# Volant5_PIC32MX_circuit_1_0.net
KiCad netlist of a schematic drawn in Altium Designer
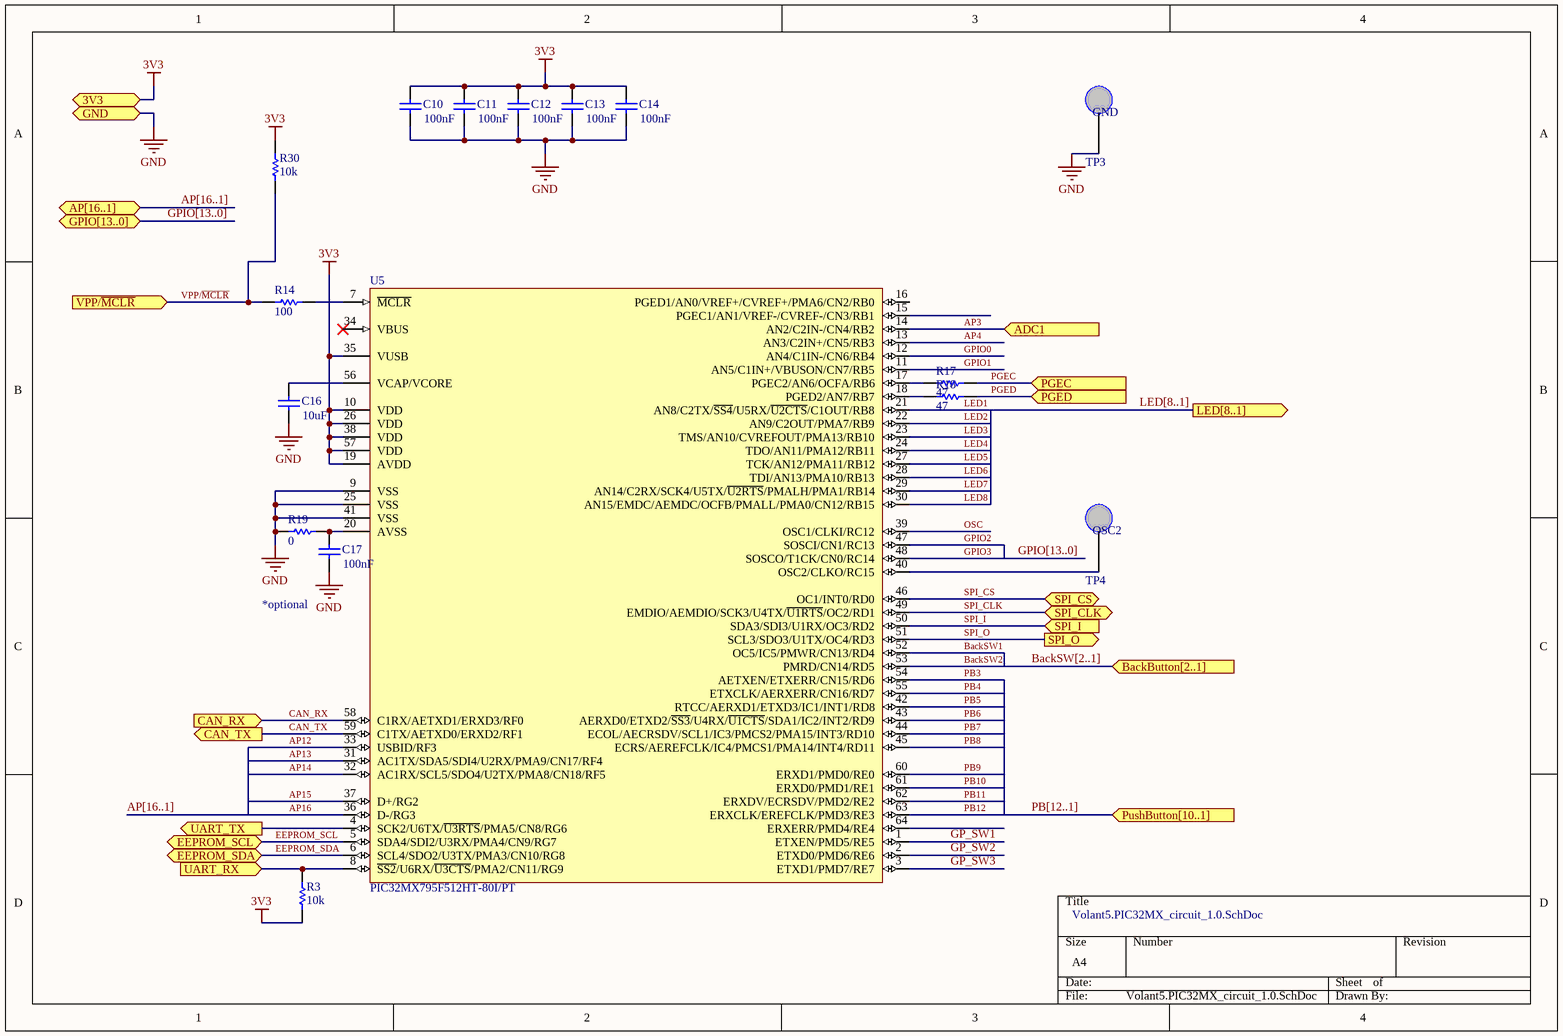
[diagram p0: Volant5.PIC32MX_circuit_1.0.SchDoc]

(export (version "E")
  (design (tool "Eeschema 10.0.6"))
  (components
    (comp (ref "C10")
      (value "100nF")
      (footprint "CS-0603")
      (fields (field (name "TOLERANCE") "10%") (field (name "Comment") "CS - CAPACITOR"))
      (libsource (lib "CHINOOK_LIBRARY") (part "CS - CAPACITOR"))
    )
    (comp (ref "C11")
      (value "100nF")
      (footprint "CS-0603")
      (fields (field (name "TOLERANCE") "10%") (field (name "Comment") "CS - CAPACITOR"))
      (libsource (lib "CHINOOK_LIBRARY") (part "CS - CAPACITOR"))
    )
    (comp (ref "C12")
      (value "100nF")
      (footprint "CS-0603")
      (fields (field (name "TOLERANCE") "10%") (field (name "Comment") "CS - CAPACITOR"))
      (libsource (lib "CHINOOK_LIBRARY") (part "CS - CAPACITOR"))
    )
    (comp (ref "C13")
      (value "100nF")
      (footprint "CS-0603")
      (fields (field (name "TOLERANCE") "10%") (field (name "Comment") "CS - CAPACITOR"))
      (libsource (lib "CHINOOK_LIBRARY") (part "CS - CAPACITOR"))
    )
    (comp (ref "C14")
      (value "100nF")
      (footprint "CS-0603")
      (fields (field (name "TOLERANCE") "10%") (field (name "Comment") "CS - CAPACITOR"))
      (libsource (lib "CHINOOK_LIBRARY") (part "CS - CAPACITOR"))
    )
    (comp (ref "C16")
      (value "10uF")
      (footprint "CS-0603")
      (fields (field (name "TOLERANCE") "10%") (field (name "Comment") "CS - CAPACITOR"))
      (libsource (lib "CHINOOK_LIBRARY") (part "CS - CAPACITOR"))
    )
    (comp (ref "C17")
      (value "100nF")
      (footprint "CS-0603")
      (fields (field (name "TOLERANCE") "10%") (field (name "Comment") "CS - CAPACITOR"))
      (libsource (lib "CHINOOK_LIBRARY") (part "CS - CAPACITOR"))
    )
    (comp (ref "R3")
      (value "10k")
      (footprint "RS-0402")
      (fields
        (field (name "TOLERANCE") "RES TOL")
        (field (name "POWER") "RES POWER")
        (field (name "Comment") "RS - RESISTOR")
      )
      (libsource (lib "CHINOOK_LIBRARY") (part "RS - RESISTOR"))
    )
    (comp (ref "R14")
      (value "100")
      (footprint "RS-0603")
      (fields
        (field (name "TOLERANCE") "RES TOL")
        (field (name "POWER") "RES POWER")
        (field (name "Comment") "RS - RESISTOR")
      )
      (libsource (lib "CHINOOK_LIBRARY") (part "RS - RESISTOR"))
    )
    (comp (ref "R17")
      (value "47")
      (footprint "RS-0603")
      (fields
        (field (name "TOLERANCE") "RES TOL")
        (field (name "POWER") "RES POWER")
        (field (name "Comment") "RS - RESISTOR")
      )
      (libsource (lib "CHINOOK_LIBRARY") (part "RS - RESISTOR"))
    )
    (comp (ref "R18")
      (value "47")
      (footprint "RS-0603")
      (fields
        (field (name "TOLERANCE") "RES TOL")
        (field (name "POWER") "RES POWER")
        (field (name "Comment") "RS - RESISTOR")
      )
      (libsource (lib "CHINOOK_LIBRARY") (part "RS - RESISTOR"))
    )
    (comp (ref "R19")
      (value "0")
      (footprint "RS-0603")
      (fields
        (field (name "TOLERANCE") "RES TOL")
        (field (name "POWER") "RES POWER")
        (field (name "Comment") "RS - RESISTOR")
      )
      (libsource (lib "CHINOOK_LIBRARY") (part "RS - RESISTOR"))
    )
    (comp (ref "R30")
      (value "10k")
      (footprint "RS-0603")
      (fields
        (field (name "TOLERANCE") "RES TOL")
        (field (name "POWER") "RES POWER")
        (field (name "Comment") "RS - RESISTOR")
      )
      (libsource (lib "CHINOOK_LIBRARY") (part "RS - RESISTOR"))
    )
    (comp (ref "TP3")
      (value "GND")
      (footprint "TP - VERTICAL")
      (libsource (lib "CHINOOK_LIBRARY") (part "TP - Test point vertical"))
    )
    (comp (ref "TP4")
      (value "OSC2")
      (footprint "TP - VERTICAL")
      (libsource (lib "CHINOOK_LIBRARY") (part "TP - Test point vertical"))
    )
    (comp (ref "U5")
      (value "PIC32MX795F512HT-80I/PT")
      (footprint "IC-TQFP-64")
      (fields (field (name "MANUFACTURER") "Microchip"))
      (libsource (lib "CHINOOK_LIBRARY") (part "IC - PIC32MX795F512HT-80I/PT"))
    )
  )
  (nets
    (net (code "22") (name "/AP3") (class "Default")
      (node (ref "U5") (pin "14") (pinfunction "AN2/C2IN-/CN4/RB2_14") (pintype "bidirectional"))
    )
    (net (code "23") (name "/AP4") (class "Default")
      (node (ref "U5") (pin "13") (pinfunction "AN3/C2IN+/CN5/RB3_13") (pintype "bidirectional"))
    )
    (net (code "24") (name "/AP12") (class "Default")
      (node (ref "U5") (pin "33") (pinfunction "USBID/RF3_33") (pintype "bidirectional"))
    )
    (net (code "25") (name "/AP13") (class "Default")
      (node (ref "U5") (pin "31") (pinfunction "AC1TX/SDA5/SDI4/U2RX/PMA9/CN17/RF4_31") (pintype "bidirectional"))
    )
    (net (code "26") (name "/AP14") (class "Default")
      (node (ref "U5") (pin "32") (pinfunction "AC1RX/SCL5/SDO4/U2TX/PMA8/CN18/RF5_32") (pintype "bidirectional"))
    )
    (net (code "27") (name "/AP15") (class "Default")
      (node (ref "U5") (pin "37") (pinfunction "D+/RG2_37") (pintype "bidirectional"))
    )
    (net (code "28") (name "/AP16") (class "Default")
      (node (ref "U5") (pin "36") (pinfunction "D-/RG3_36") (pintype "bidirectional"))
    )
    (net (code "30") (name "/BackSW1") (class "Default")
      (node (ref "U5") (pin "52") (pinfunction "OC5/IC5/PMWR/CN13/RD4_52") (pintype "bidirectional"))
    )
    (net (code "31") (name "/BackSW2") (class "Default")
      (node (ref "U5") (pin "53") (pinfunction "PMRD/CN14/RD5_53") (pintype "bidirectional"))
    )
    (net (code "33") (name "/CAN_RX") (class "Default")
      (node (ref "U5") (pin "58") (pinfunction "C1RX/AETXD1/ERXD3/RF0_58") (pintype "bidirectional"))
    )
    (net (code "34") (name "/CAN_TX") (class "Default")
      (node (ref "U5") (pin "59") (pinfunction "C1TX/AETXD0/ERXD2/RF1_59") (pintype "bidirectional"))
    )
    (net (code "35") (name "/EEPROM_SCL") (class "Default")
      (node (ref "U5") (pin "5") (pinfunction "SDA4/SDI2/U3RX/PMA4/CN9/RG7_5") (pintype "bidirectional"))
    )
    (net (code "36") (name "/EEPROM_SDA") (class "Default")
      (node (ref "U5") (pin "6") (pinfunction "SCL4/SDO2/U3TX/PMA3/CN10/RG8_6") (pintype "bidirectional"))
    )
    (net (code "37") (name "/GPIO0") (class "Default")
      (node (ref "U5") (pin "12") (pinfunction "AN4/C1IN-/CN6/RB4_12") (pintype "bidirectional"))
    )
    (net (code "38") (name "/GPIO1") (class "Default")
      (node (ref "U5") (pin "11") (pinfunction "AN5/C1IN+/VBUSON/CN7/RB5_11") (pintype "bidirectional"))
    )
    (net (code "39") (name "/GPIO2") (class "Default")
      (node (ref "U5") (pin "47") (pinfunction "SOSCI/CN1/RC13_47") (pintype "bidirectional"))
    )
    (net (code "40") (name "/GPIO3") (class "Default")
      (node (ref "U5") (pin "48") (pinfunction "SOSCO/T1CK/CN0/RC14_48") (pintype "bidirectional"))
    )
    (net (code "42") (name "/GP_SW1") (class "Default")
      (node (ref "U5") (pin "1") (pinfunction "ETXEN/PMD5/RE5_1") (pintype "bidirectional"))
    )
    (net (code "43") (name "/GP_SW2") (class "Default")
      (node (ref "U5") (pin "2") (pinfunction "ETXD0/PMD6/RE6_2") (pintype "bidirectional"))
    )
    (net (code "44") (name "/GP_SW3") (class "Default")
      (node (ref "U5") (pin "3") (pinfunction "ETXD1/PMD7/RE7_3") (pintype "bidirectional"))
    )
    (net (code "45") (name "/LED1") (class "Default")
      (node (ref "U5") (pin "21") (pinfunction "AN8/C2TX/~{SS4}/U5RX/~{U2CTS}/C1OUT/RB8_21") (pintype "bidirectional"))
    )
    (net (code "46") (name "/LED2") (class "Default")
      (node (ref "U5") (pin "22") (pinfunction "AN9/C2OUT/PMA7/RB9_22") (pintype "bidirectional"))
    )
    (net (code "47") (name "/LED3") (class "Default")
      (node (ref "U5") (pin "23") (pinfunction "TMS/AN10/CVREFOUT/PMA13/RB10_23") (pintype "bidirectional"))
    )
    (net (code "48") (name "/LED4") (class "Default")
      (node (ref "U5") (pin "24") (pinfunction "TDO/AN11/PMA12/RB11_24") (pintype "bidirectional"))
    )
    (net (code "49") (name "/LED5") (class "Default")
      (node (ref "U5") (pin "27") (pinfunction "TCK/AN12/PMA11/RB12_27") (pintype "bidirectional"))
    )
    (net (code "50") (name "/LED6") (class "Default")
      (node (ref "U5") (pin "28") (pinfunction "TDI/AN13/PMA10/RB13_28") (pintype "bidirectional"))
    )
    (net (code "51") (name "/LED7") (class "Default")
      (node (ref "U5") (pin "29") (pinfunction "AN14/C2RX/SCK4/U5TX/~{U2RTS}/PMALH/PMA1/RB14_29") (pintype "bidirectional"))
    )
    (net (code "52") (name "/LED8") (class "Default")
      (node (ref "U5") (pin "30") (pinfunction "AN15/EMDC/AEMDC/OCFB/PMALL/PMA0/CN12/RB15_30") (pintype "bidirectional"))
    )
    (net (code "54") (name "/OSC") (class "Default")
      (node (ref "U5") (pin "39") (pinfunction "OSC1/CLKI/RC12_39") (pintype "bidirectional"))
    )
    (net (code "55") (name "/PB3") (class "Default")
      (node (ref "U5") (pin "54") (pinfunction "AETXEN/ETXERR/CN15/RD6_54") (pintype "bidirectional"))
    )
    (net (code "56") (name "/PB4") (class "Default")
      (node (ref "U5") (pin "55") (pinfunction "ETXCLK/AERXERR/CN16/RD7_55") (pintype "bidirectional"))
    )
    (net (code "57") (name "/PB5") (class "Default")
      (node (ref "U5") (pin "42") (pinfunction "RTCC/AERXD1/ETXD3/IC1/INT1/RD8_42") (pintype "bidirectional"))
    )
    (net (code "58") (name "/PB6") (class "Default")
      (node (ref "U5") (pin "43") (pinfunction "AERXD0/ETXD2/~{SS3}/U4RX/~{U1CTS}/SDA1/IC2/INT2/RD9_43") (pintype "bidirectional"))
    )
    (net (code "59") (name "/PB7") (class "Default")
      (node (ref "U5") (pin "44") (pinfunction "ECOL/AECRSDV/SCL1/IC3/PMCS2/PMA15/INT3/RD10_44") (pintype "bidirectional"))
    )
    (net (code "60") (name "/PB8") (class "Default")
      (node (ref "U5") (pin "45") (pinfunction "ECRS/AEREFCLK/IC4/PMCS1/PMA14/INT4/RD11_45") (pintype "bidirectional"))
    )
    (net (code "61") (name "/PB9") (class "Default")
      (node (ref "U5") (pin "60") (pinfunction "ERXD1/PMD0/RE0_60") (pintype "bidirectional"))
    )
    (net (code "62") (name "/PB10") (class "Default")
      (node (ref "U5") (pin "61") (pinfunction "ERXD0/PMD1/RE1_61") (pintype "bidirectional"))
    )
    (net (code "63") (name "/PB11") (class "Default")
      (node (ref "U5") (pin "62") (pinfunction "ERXDV/ECRSDV/PMD2/RE2_62") (pintype "bidirectional"))
    )
    (net (code "64") (name "/PB12") (class "Default")
      (node (ref "U5") (pin "63") (pinfunction "ERXCLK/EREFCLK/PMD3/RE3_63") (pintype "bidirectional"))
    )
    (net (code "66") (name "/PGEC") (class "Default")
      (node (ref "R17") (pin "1") (pinfunction "1_1") (pintype "passive"))
    )
    (net (code "67") (name "/PGED") (class "Default")
      (node (ref "R18") (pin "1") (pinfunction "1_1") (pintype "passive"))
    )
    (net (code "68") (name "/SPI_CLK") (class "Default")
      (node (ref "U5") (pin "49") (pinfunction "EMDIO/AEMDIO/SCK3/U4TX/~{U1RTS}/OC2/RD1_49") (pintype "bidirectional"))
    )
    (net (code "69") (name "/SPI_CS") (class "Default")
      (node (ref "U5") (pin "46") (pinfunction "OC1/INT0/RD0_46") (pintype "bidirectional"))
    )
    (net (code "70") (name "/SPI_I") (class "Default")
      (node (ref "U5") (pin "50") (pinfunction "SDA3/SDI3/U1RX/OC3/RD2_50") (pintype "bidirectional"))
    )
    (net (code "71") (name "/SPI_O") (class "Default")
      (node (ref "U5") (pin "51") (pinfunction "SCL3/SDO3/U1TX/OC4/RD3_51") (pintype "bidirectional"))
    )
    (net (code "72") (name "/UART_RX") (class "Default")
      (node (ref "R3") (pin "2") (pinfunction "2_2") (pintype "passive"))
      (node (ref "U5") (pin "8") (pinfunction "~{SS2}/U6RX/~{U3CTS}/PMA2/CN11/RG9_8") (pintype "bidirectional"))
    )
    (net (code "73") (name "/UART_TX") (class "Default")
      (node (ref "U5") (pin "4") (pinfunction "SCK2/U6TX/~{U3RTS}/PMA5/CN8/RG6_4") (pintype "bidirectional"))
    )
    (net (code "74") (name "/VPP{slash}~{MCLR}") (class "Default")
      (node (ref "R14") (pin "2") (pinfunction "2_2") (pintype "passive"))
      (node (ref "R30") (pin "1") (pinfunction "1_1") (pintype "passive"))
    )
    (net (code "75") (name "3V3") (class "Default")
      (node (ref "C10") (pin "2") (pinfunction "2_2") (pintype "passive"))
      (node (ref "C11") (pin "2") (pinfunction "2_2") (pintype "passive"))
      (node (ref "C12") (pin "2") (pinfunction "2_2") (pintype "passive"))
      (node (ref "C13") (pin "2") (pinfunction "2_2") (pintype "passive"))
      (node (ref "C14") (pin "2") (pinfunction "2_2") (pintype "passive"))
      (node (ref "R3") (pin "1") (pinfunction "1_1") (pintype "passive"))
      (node (ref "R30") (pin "2") (pinfunction "2_2") (pintype "passive"))
      (node (ref "U5") (pin "10") (pinfunction "VDD_10") (pintype "power_in"))
      (node (ref "U5") (pin "19") (pinfunction "AVDD_19") (pintype "power_in"))
      (node (ref "U5") (pin "26") (pinfunction "VDD_26") (pintype "power_in"))
      (node (ref "U5") (pin "35") (pinfunction "VUSB_35") (pintype "power_in"))
      (node (ref "U5") (pin "38") (pinfunction "VDD_38") (pintype "power_in"))
      (node (ref "U5") (pin "57") (pinfunction "VDD_57") (pintype "power_in"))
    )
    (net (code "76") (name "GND") (class "Default")
      (node (ref "C10") (pin "1") (pinfunction "1_1") (pintype "passive"))
      (node (ref "C11") (pin "1") (pinfunction "1_1") (pintype "passive"))
      (node (ref "C12") (pin "1") (pinfunction "1_1") (pintype "passive"))
      (node (ref "C13") (pin "1") (pinfunction "1_1") (pintype "passive"))
      (node (ref "C14") (pin "1") (pinfunction "1_1") (pintype "passive"))
      (node (ref "C16") (pin "1") (pinfunction "1_1") (pintype "passive"))
      (node (ref "C17") (pin "1") (pinfunction "1_1") (pintype "passive"))
      (node (ref "R19") (pin "2") (pinfunction "2_2") (pintype "passive"))
      (node (ref "TP3") (pin "1") (pinfunction "1_1") (pintype "passive"))
      (node (ref "U5") (pin "25") (pinfunction "VSS_25") (pintype "power_in"))
      (node (ref "U5") (pin "41") (pinfunction "VSS_41") (pintype "power_in"))
      (node (ref "U5") (pin "9") (pinfunction "VSS_9") (pintype "power_in"))
    )
    (net (code "77") (name "Net-(U5-AVSS)") (class "Default")
      (node (ref "C17") (pin "2") (pinfunction "2_2") (pintype "passive"))
      (node (ref "R19") (pin "1") (pinfunction "1_1") (pintype "passive"))
      (node (ref "U5") (pin "20") (pinfunction "AVSS_20") (pintype "power_in"))
    )
    (net (code "78") (name "Net-(U5-OSC2{slash}CLKO{slash}RC15)") (class "Default")
      (node (ref "TP4") (pin "1") (pinfunction "1_1") (pintype "passive"))
      (node (ref "U5") (pin "40") (pinfunction "OSC2/CLKO/RC15_40") (pintype "bidirectional"))
    )
    (net (code "79") (name "Net-(U5-PGEC2{slash}AN6{slash}OCFA{slash}RB6)") (class "Default")
      (node (ref "R17") (pin "2") (pinfunction "2_2") (pintype "passive"))
      (node (ref "U5") (pin "17") (pinfunction "PGEC2/AN6/OCFA/RB6_17") (pintype "bidirectional"))
    )
    (net (code "80") (name "Net-(U5-PGED2{slash}AN7{slash}RB7)") (class "Default")
      (node (ref "R18") (pin "2") (pinfunction "2_2") (pintype "passive"))
      (node (ref "U5") (pin "18") (pinfunction "PGED2/AN7/RB7_18") (pintype "bidirectional"))
    )
    (net (code "81") (name "Net-(U5-VCAP{slash}VCORE)") (class "Default")
      (node (ref "C16") (pin "2") (pinfunction "2_2") (pintype "passive"))
      (node (ref "U5") (pin "56") (pinfunction "VCAP/VCORE_56") (pintype "power_in"))
    )
    (net (code "82") (name "Net-(U5-~{MCLR})") (class "Default")
      (node (ref "R14") (pin "1") (pinfunction "1_1") (pintype "passive"))
      (node (ref "U5") (pin "7") (pinfunction "~{MCLR}_7") (pintype "input"))
    )
    (net (code "83") (name "unconnected-(U5-ERXERR{slash}PMD4{slash}RE4-Pad64)") (class "Default")
      (node (ref "U5") (pin "64") (pinfunction "ERXERR/PMD4/RE4_64") (pintype "bidirectional"))
    )
    (net (code "84") (name "unconnected-(U5-PGEC1{slash}AN1{slash}VREF-{slash}CVREF-{slash}CN3{slash}RB1-Pad15)") (class "Default")
      (node (ref "U5") (pin "15") (pinfunction "PGEC1/AN1/VREF-/CVREF-/CN3/RB1_15") (pintype "bidirectional"))
    )
    (net (code "85") (name "unconnected-(U5-PGED1{slash}AN0{slash}VREF+{slash}CVREF+{slash}PMA6{slash}CN2{slash}RB0-Pad16)") (class "Default")
      (node (ref "U5") (pin "16") (pinfunction "PGED1/AN0/VREF+/CVREF+/PMA6/CN2/RB0_16") (pintype "bidirectional"))
    )
    (net (code "86") (name "unconnected-(U5-VBUS-Pad34)") (class "Default")
      (node (ref "U5") (pin "34") (pinfunction "VBUS_34") (pintype "input+no_connect"))
    )
  )
)
